# Wuhu_V1.net
KiCad netlist of a schematic drawn in Altium Designer
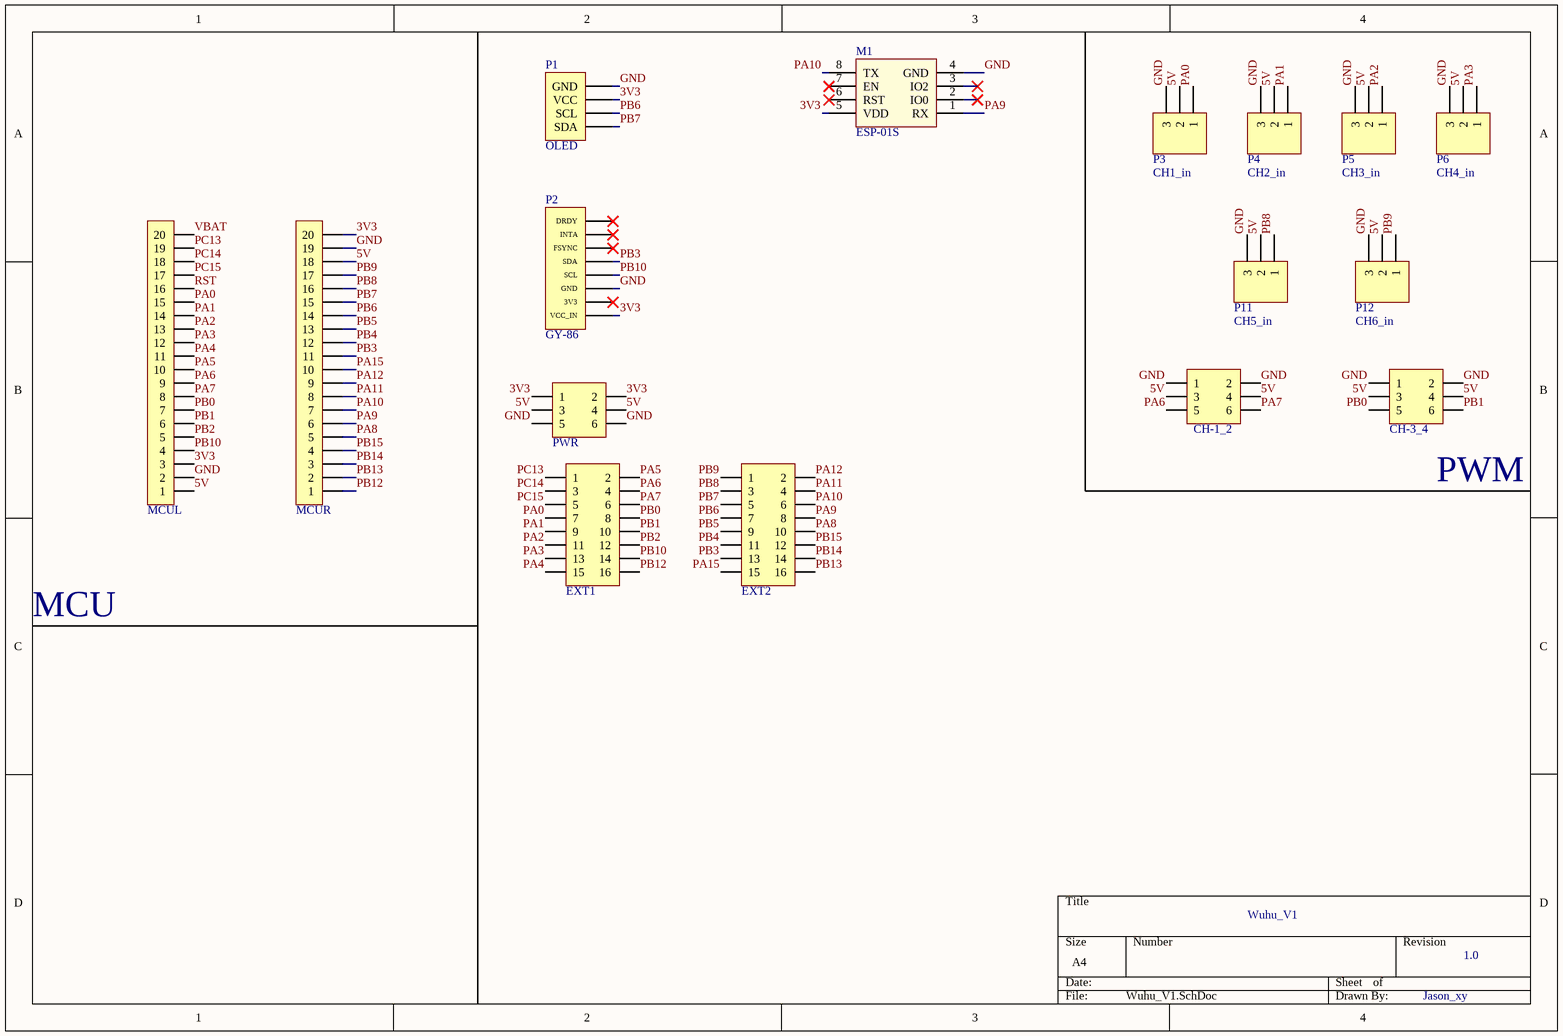
[diagram p0: Wuhu_V1.SchDoc]

(export (version "E")
  (design (tool "Eeschema 10.0.6"))
  (components
    (comp (ref "CH-1_2")
      (value "Header3X2")
      (footprint "HDR2.54-WI-2x3P")
      (description "3*2P接插件")
      (fields (field (name "版权归属") "源创客"))
      (libsource (lib "4.5   - 接插件-脚距2.54") (part "Header 3X2"))
    )
    (comp (ref "CH-3_4")
      (value "Header3X2")
      (footprint "HDR2.54-WI-2x3P")
      (description "3*2P接插件")
      (fields (field (name "版权归属") "源创客"))
      (libsource (lib "4.5   - 接插件-脚距2.54") (part "Header 3X2"))
    )
    (comp (ref "EXT1")
      (value "Header 8X2")
      (footprint "HDR2.54-M-LS-2x8P")
      (description "8*2P接插件")
      (fields (field (name "版权归属") "源创客"))
      (libsource (lib "4.5   - 接插件-脚距2.54") (part "Header 8X2"))
    )
    (comp (ref "EXT2")
      (value "Header 8X2")
      (footprint "HDR2.54-M-LS-2x8P")
      (description "8*2P接插件")
      (fields (field (name "版权归属") "源创客"))
      (libsource (lib "4.5   - 接插件-脚距2.54") (part "Header 8X2"))
    )
    (comp (ref "M1")
      (value "ESP-01S")
      (footprint "ESP-01&01S Module")
      (libsource (lib "ESP-01&01S Module") (part "ESP-01&01S Module"))
    )
    (comp (ref "MCUL")
      (value "HDR-1X20")
      (footprint "HDR2.54-M-LI-20P")
      (description "20P接插件")
      (fields (field (name "版权归属") "源创客"))
      (libsource (lib "4.5   - 接插件-脚距2.54") (part "Header 20"))
    )
    (comp (ref "MCUR")
      (value "HDR-1X20")
      (footprint "HDR2.54-M-LI-20P")
      (description "20P接插件")
      (fields (field (name "版权归属") "源创客"))
      (libsource (lib "4.5   - 接插件-脚距2.54") (part "Header 20"))
    )
    (comp (ref "P1")
      (value "OLED")
      (footprint "排针-排母:HDR2.54-M-LI-4P")
      (description "Header, 4-Pin")
      (fields (field (name "PUBLISHER") "Altium Limited"))
      (libsource (lib "Miscellaneous Connectors") (part "MHDR1X4"))
    )
    (comp (ref "P2")
      (value "GY-86")
      (footprint "GY-86")
      (description "Header, 8-Pin")
      (fields (field (name "PUBLISHER") "Altium Limited"))
      (libsource (lib "Miscellaneous Connectors") (part "MHDR1X8"))
    )
    (comp (ref "P3")
      (value "CH1_in")
      (footprint "HDR2.54-WI-3P")
      (description "Header, 3-Pin")
      (fields (field (name "PUBLISHER") "Altium Limited"))
      (libsource (lib "Miscellaneous Connectors") (part "MHDR1X3"))
    )
    (comp (ref "P4")
      (value "CH2_in")
      (footprint "HDR2.54-WI-3P")
      (description "Header, 3-Pin")
      (fields (field (name "PUBLISHER") "Altium Limited"))
      (libsource (lib "Miscellaneous Connectors") (part "MHDR1X3"))
    )
    (comp (ref "P5")
      (value "CH3_in")
      (footprint "HDR2.54-WI-3P")
      (description "Header, 3-Pin")
      (fields (field (name "PUBLISHER") "Altium Limited"))
      (libsource (lib "Miscellaneous Connectors") (part "MHDR1X3"))
    )
    (comp (ref "P6")
      (value "CH4_in")
      (footprint "HDR2.54-WI-3P")
      (description "Header, 3-Pin")
      (fields (field (name "PUBLISHER") "Altium Limited"))
      (libsource (lib "Miscellaneous Connectors") (part "MHDR1X3"))
    )
    (comp (ref "P11")
      (value "CH5_in")
      (footprint "HDR2.54-WI-3P")
      (description "Header, 3-Pin")
      (fields (field (name "PUBLISHER") "Altium Limited"))
      (libsource (lib "Miscellaneous Connectors") (part "MHDR1X3"))
    )
    (comp (ref "P12")
      (value "CH6_in")
      (footprint "HDR2.54-WI-3P")
      (description "Header, 3-Pin")
      (fields (field (name "PUBLISHER") "Altium Limited"))
      (libsource (lib "Miscellaneous Connectors") (part "MHDR1X3"))
    )
    (comp (ref "PWR")
      (value "Header3X2")
      (footprint "HDR2.54-M-LS-2x3P")
      (description "3*2P接插件")
      (fields (field (name "版权归属") "源创客"))
      (libsource (lib "4.5   - 接插件-脚距2.54") (part "Header 3X2"))
    )
  )
  (nets
    (net (code "1") (name "/3V3") (class "Default")
      (node (ref "M1") (pin "5") (pinfunction "VDD_5") (pintype "passive"))
      (node (ref "MCUL") (pin "3") (pinfunction "3_3") (pintype "passive"))
      (node (ref "MCUR") (pin "20") (pinfunction "20_20") (pintype "passive"))
      (node (ref "P1") (pin "3") (pinfunction "VCC_3") (pintype "passive"))
      (node (ref "P2") (pin "1") (pinfunction "VCC_IN_1") (pintype "passive"))
      (node (ref "PWR") (pin "1") (pinfunction "1_1") (pintype "passive"))
      (node (ref "PWR") (pin "2") (pinfunction "2_2") (pintype "passive"))
    )
    (net (code "2") (name "/5V") (class "Default")
      (node (ref "CH-1_2") (pin "3") (pinfunction "3_3") (pintype "passive"))
      (node (ref "CH-1_2") (pin "4") (pinfunction "4_4") (pintype "passive"))
      (node (ref "CH-3_4") (pin "3") (pinfunction "3_3") (pintype "passive"))
      (node (ref "CH-3_4") (pin "4") (pinfunction "4_4") (pintype "passive"))
      (node (ref "MCUL") (pin "1") (pinfunction "1_1") (pintype "passive"))
      (node (ref "MCUR") (pin "18") (pinfunction "18_18") (pintype "passive"))
      (node (ref "P11") (pin "2") (pinfunction "2_2") (pintype "passive"))
      (node (ref "P12") (pin "2") (pinfunction "2_2") (pintype "passive"))
      (node (ref "P3") (pin "2") (pinfunction "2_2") (pintype "passive"))
      (node (ref "P4") (pin "2") (pinfunction "2_2") (pintype "passive"))
      (node (ref "P5") (pin "2") (pinfunction "2_2") (pintype "passive"))
      (node (ref "P6") (pin "2") (pinfunction "2_2") (pintype "passive"))
      (node (ref "PWR") (pin "3") (pinfunction "3_3") (pintype "passive"))
      (node (ref "PWR") (pin "4") (pinfunction "4_4") (pintype "passive"))
    )
    (net (code "3") (name "/GND") (class "Default")
      (node (ref "CH-1_2") (pin "1") (pinfunction "1_1") (pintype "passive"))
      (node (ref "CH-1_2") (pin "2") (pinfunction "2_2") (pintype "passive"))
      (node (ref "CH-3_4") (pin "1") (pinfunction "1_1") (pintype "passive"))
      (node (ref "CH-3_4") (pin "2") (pinfunction "2_2") (pintype "passive"))
      (node (ref "M1") (pin "4") (pinfunction "GND_4") (pintype "passive"))
      (node (ref "MCUL") (pin "2") (pinfunction "2_2") (pintype "passive"))
      (node (ref "MCUR") (pin "19") (pinfunction "19_19") (pintype "passive"))
      (node (ref "P1") (pin "4") (pinfunction "GND_4") (pintype "passive"))
      (node (ref "P11") (pin "3") (pinfunction "3_3") (pintype "passive"))
      (node (ref "P12") (pin "3") (pinfunction "3_3") (pintype "passive"))
      (node (ref "P2") (pin "3") (pinfunction "GND_3") (pintype "passive"))
      (node (ref "P3") (pin "3") (pinfunction "3_3") (pintype "passive"))
      (node (ref "P4") (pin "3") (pinfunction "3_3") (pintype "passive"))
      (node (ref "P5") (pin "3") (pinfunction "3_3") (pintype "passive"))
      (node (ref "P6") (pin "3") (pinfunction "3_3") (pintype "passive"))
      (node (ref "PWR") (pin "5") (pinfunction "5_5") (pintype "passive"))
      (node (ref "PWR") (pin "6") (pinfunction "6_6") (pintype "passive"))
    )
    (net (code "4") (name "/PA0") (class "Default")
      (node (ref "EXT1") (pin "7") (pinfunction "7_7") (pintype "passive"))
      (node (ref "MCUL") (pin "15") (pinfunction "15_15") (pintype "passive"))
      (node (ref "P3") (pin "1") (pinfunction "1_1") (pintype "passive"))
    )
    (net (code "5") (name "/PA1") (class "Default")
      (node (ref "EXT1") (pin "9") (pinfunction "9_9") (pintype "passive"))
      (node (ref "MCUL") (pin "14") (pinfunction "14_14") (pintype "passive"))
      (node (ref "P4") (pin "1") (pinfunction "1_1") (pintype "passive"))
    )
    (net (code "6") (name "/PA2") (class "Default")
      (node (ref "EXT1") (pin "11") (pinfunction "11_11") (pintype "passive"))
      (node (ref "MCUL") (pin "13") (pinfunction "13_13") (pintype "passive"))
      (node (ref "P5") (pin "1") (pinfunction "1_1") (pintype "passive"))
    )
    (net (code "7") (name "/PA3") (class "Default")
      (node (ref "EXT1") (pin "13") (pinfunction "13_13") (pintype "passive"))
      (node (ref "MCUL") (pin "12") (pinfunction "12_12") (pintype "passive"))
      (node (ref "P6") (pin "1") (pinfunction "1_1") (pintype "passive"))
    )
    (net (code "8") (name "/PA4") (class "Default")
      (node (ref "EXT1") (pin "15") (pinfunction "15_15") (pintype "passive"))
      (node (ref "MCUL") (pin "11") (pinfunction "11_11") (pintype "passive"))
    )
    (net (code "9") (name "/PA5") (class "Default")
      (node (ref "EXT1") (pin "2") (pinfunction "2_2") (pintype "passive"))
      (node (ref "MCUL") (pin "10") (pinfunction "10_10") (pintype "passive"))
    )
    (net (code "10") (name "/PA6") (class "Default")
      (node (ref "CH-1_2") (pin "5") (pinfunction "5_5") (pintype "passive"))
      (node (ref "EXT1") (pin "4") (pinfunction "4_4") (pintype "passive"))
      (node (ref "MCUL") (pin "9") (pinfunction "9_9") (pintype "passive"))
    )
    (net (code "11") (name "/PA7") (class "Default")
      (node (ref "CH-1_2") (pin "6") (pinfunction "6_6") (pintype "passive"))
      (node (ref "EXT1") (pin "6") (pinfunction "6_6") (pintype "passive"))
      (node (ref "MCUL") (pin "8") (pinfunction "8_8") (pintype "passive"))
    )
    (net (code "12") (name "/PA8") (class "Default")
      (node (ref "EXT2") (pin "10") (pinfunction "10_10") (pintype "passive"))
      (node (ref "MCUR") (pin "5") (pinfunction "5_5") (pintype "passive"))
    )
    (net (code "13") (name "/PA9") (class "Default")
      (node (ref "EXT2") (pin "8") (pinfunction "8_8") (pintype "passive"))
      (node (ref "M1") (pin "1") (pinfunction "RX_1") (pintype "passive"))
      (node (ref "MCUR") (pin "6") (pinfunction "6_6") (pintype "passive"))
    )
    (net (code "14") (name "/PA10") (class "Default")
      (node (ref "EXT2") (pin "6") (pinfunction "6_6") (pintype "passive"))
      (node (ref "M1") (pin "8") (pinfunction "TX_8") (pintype "passive"))
      (node (ref "MCUR") (pin "7") (pinfunction "7_7") (pintype "passive"))
    )
    (net (code "15") (name "/PA11") (class "Default")
      (node (ref "EXT2") (pin "4") (pinfunction "4_4") (pintype "passive"))
      (node (ref "MCUR") (pin "8") (pinfunction "8_8") (pintype "passive"))
    )
    (net (code "16") (name "/PA12") (class "Default")
      (node (ref "EXT2") (pin "2") (pinfunction "2_2") (pintype "passive"))
      (node (ref "MCUR") (pin "9") (pinfunction "9_9") (pintype "passive"))
    )
    (net (code "17") (name "/PA15") (class "Default")
      (node (ref "EXT2") (pin "15") (pinfunction "15_15") (pintype "passive"))
      (node (ref "MCUR") (pin "10") (pinfunction "10_10") (pintype "passive"))
    )
    (net (code "18") (name "/PB0") (class "Default")
      (node (ref "CH-3_4") (pin "5") (pinfunction "5_5") (pintype "passive"))
      (node (ref "EXT1") (pin "8") (pinfunction "8_8") (pintype "passive"))
      (node (ref "MCUL") (pin "7") (pinfunction "7_7") (pintype "passive"))
    )
    (net (code "19") (name "/PB1") (class "Default")
      (node (ref "CH-3_4") (pin "6") (pinfunction "6_6") (pintype "passive"))
      (node (ref "EXT1") (pin "10") (pinfunction "10_10") (pintype "passive"))
      (node (ref "MCUL") (pin "6") (pinfunction "6_6") (pintype "passive"))
    )
    (net (code "20") (name "/PB2") (class "Default")
      (node (ref "EXT1") (pin "12") (pinfunction "12_12") (pintype "passive"))
      (node (ref "MCUL") (pin "5") (pinfunction "5_5") (pintype "passive"))
    )
    (net (code "21") (name "/PB3") (class "Default")
      (node (ref "EXT2") (pin "13") (pinfunction "13_13") (pintype "passive"))
      (node (ref "MCUR") (pin "11") (pinfunction "11_11") (pintype "passive"))
      (node (ref "P2") (pin "5") (pinfunction "SDA_5") (pintype "passive"))
    )
    (net (code "22") (name "/PB4") (class "Default")
      (node (ref "EXT2") (pin "11") (pinfunction "11_11") (pintype "passive"))
      (node (ref "MCUR") (pin "12") (pinfunction "12_12") (pintype "passive"))
    )
    (net (code "23") (name "/PB5") (class "Default")
      (node (ref "EXT2") (pin "9") (pinfunction "9_9") (pintype "passive"))
      (node (ref "MCUR") (pin "13") (pinfunction "13_13") (pintype "passive"))
    )
    (net (code "24") (name "/PB6") (class "Default")
      (node (ref "EXT2") (pin "7") (pinfunction "7_7") (pintype "passive"))
      (node (ref "MCUR") (pin "14") (pinfunction "14_14") (pintype "passive"))
      (node (ref "P1") (pin "2") (pinfunction "SCL_2") (pintype "passive"))
    )
    (net (code "25") (name "/PB7") (class "Default")
      (node (ref "EXT2") (pin "5") (pinfunction "5_5") (pintype "passive"))
      (node (ref "MCUR") (pin "15") (pinfunction "15_15") (pintype "passive"))
      (node (ref "P1") (pin "1") (pinfunction "SDA_1") (pintype "passive"))
    )
    (net (code "26") (name "/PB8") (class "Default")
      (node (ref "EXT2") (pin "3") (pinfunction "3_3") (pintype "passive"))
      (node (ref "MCUR") (pin "16") (pinfunction "16_16") (pintype "passive"))
      (node (ref "P11") (pin "1") (pinfunction "1_1") (pintype "passive"))
    )
    (net (code "27") (name "/PB9") (class "Default")
      (node (ref "EXT2") (pin "1") (pinfunction "1_1") (pintype "passive"))
      (node (ref "MCUR") (pin "17") (pinfunction "17_17") (pintype "passive"))
      (node (ref "P12") (pin "1") (pinfunction "1_1") (pintype "passive"))
    )
    (net (code "28") (name "/PB10") (class "Default")
      (node (ref "EXT1") (pin "14") (pinfunction "14_14") (pintype "passive"))
      (node (ref "MCUL") (pin "4") (pinfunction "4_4") (pintype "passive"))
      (node (ref "P2") (pin "4") (pinfunction "SCL_4") (pintype "passive"))
    )
    (net (code "29") (name "/PB12") (class "Default")
      (node (ref "EXT1") (pin "16") (pinfunction "16_16") (pintype "passive"))
      (node (ref "MCUR") (pin "1") (pinfunction "1_1") (pintype "passive"))
    )
    (net (code "30") (name "/PB13") (class "Default")
      (node (ref "EXT2") (pin "16") (pinfunction "16_16") (pintype "passive"))
      (node (ref "MCUR") (pin "2") (pinfunction "2_2") (pintype "passive"))
    )
    (net (code "31") (name "/PB14") (class "Default")
      (node (ref "EXT2") (pin "14") (pinfunction "14_14") (pintype "passive"))
      (node (ref "MCUR") (pin "3") (pinfunction "3_3") (pintype "passive"))
    )
    (net (code "32") (name "/PB15") (class "Default")
      (node (ref "EXT2") (pin "12") (pinfunction "12_12") (pintype "passive"))
      (node (ref "MCUR") (pin "4") (pinfunction "4_4") (pintype "passive"))
    )
    (net (code "33") (name "/PC13") (class "Default")
      (node (ref "EXT1") (pin "1") (pinfunction "1_1") (pintype "passive"))
      (node (ref "MCUL") (pin "19") (pinfunction "19_19") (pintype "passive"))
    )
    (net (code "34") (name "/PC14") (class "Default")
      (node (ref "EXT1") (pin "3") (pinfunction "3_3") (pintype "passive"))
      (node (ref "MCUL") (pin "18") (pinfunction "18_18") (pintype "passive"))
    )
    (net (code "35") (name "/PC15") (class "Default")
      (node (ref "EXT1") (pin "5") (pinfunction "5_5") (pintype "passive"))
      (node (ref "MCUL") (pin "17") (pinfunction "17_17") (pintype "passive"))
    )
    (net (code "36") (name "/RST") (class "Default")
      (node (ref "MCUL") (pin "16") (pinfunction "16_16") (pintype "passive"))
    )
    (net (code "37") (name "/VBAT") (class "Default")
      (node (ref "MCUL") (pin "20") (pinfunction "20_20") (pintype "passive"))
    )
    (net (code "38") (name "unconnected-(M1-EN-Pad7)") (class "Default")
      (node (ref "M1") (pin "7") (pinfunction "EN_7") (pintype "passive+no_connect"))
    )
    (net (code "39") (name "unconnected-(M1-IO0-Pad2)") (class "Default")
      (node (ref "M1") (pin "2") (pinfunction "IO0_2") (pintype "passive+no_connect"))
    )
    (net (code "40") (name "unconnected-(M1-IO2-Pad3)") (class "Default")
      (node (ref "M1") (pin "3") (pinfunction "IO2_3") (pintype "passive+no_connect"))
    )
    (net (code "41") (name "unconnected-(M1-RST-Pad6)") (class "Default")
      (node (ref "M1") (pin "6") (pinfunction "RST_6") (pintype "passive+no_connect"))
    )
    (net (code "42") (name "unconnected-(P2-3V3-Pad2)") (class "Default")
      (node (ref "P2") (pin "2") (pinfunction "3V3_2") (pintype "passive+no_connect"))
    )
    (net (code "43") (name "unconnected-(P2-DRDY-Pad8)") (class "Default")
      (node (ref "P2") (pin "8") (pinfunction "DRDY_8") (pintype "passive+no_connect"))
    )
    (net (code "44") (name "unconnected-(P2-FSYNC-Pad6)") (class "Default")
      (node (ref "P2") (pin "6") (pinfunction "FSYNC_6") (pintype "passive+no_connect"))
    )
    (net (code "45") (name "unconnected-(P2-INTA-Pad7)") (class "Default")
      (node (ref "P2") (pin "7") (pinfunction "INTA_7") (pintype "passive+no_connect"))
    )
  )
)
